# flexdrive_atlas_stack_draft_01.net
KiCad netlist of a schematic drawn in EAGLE
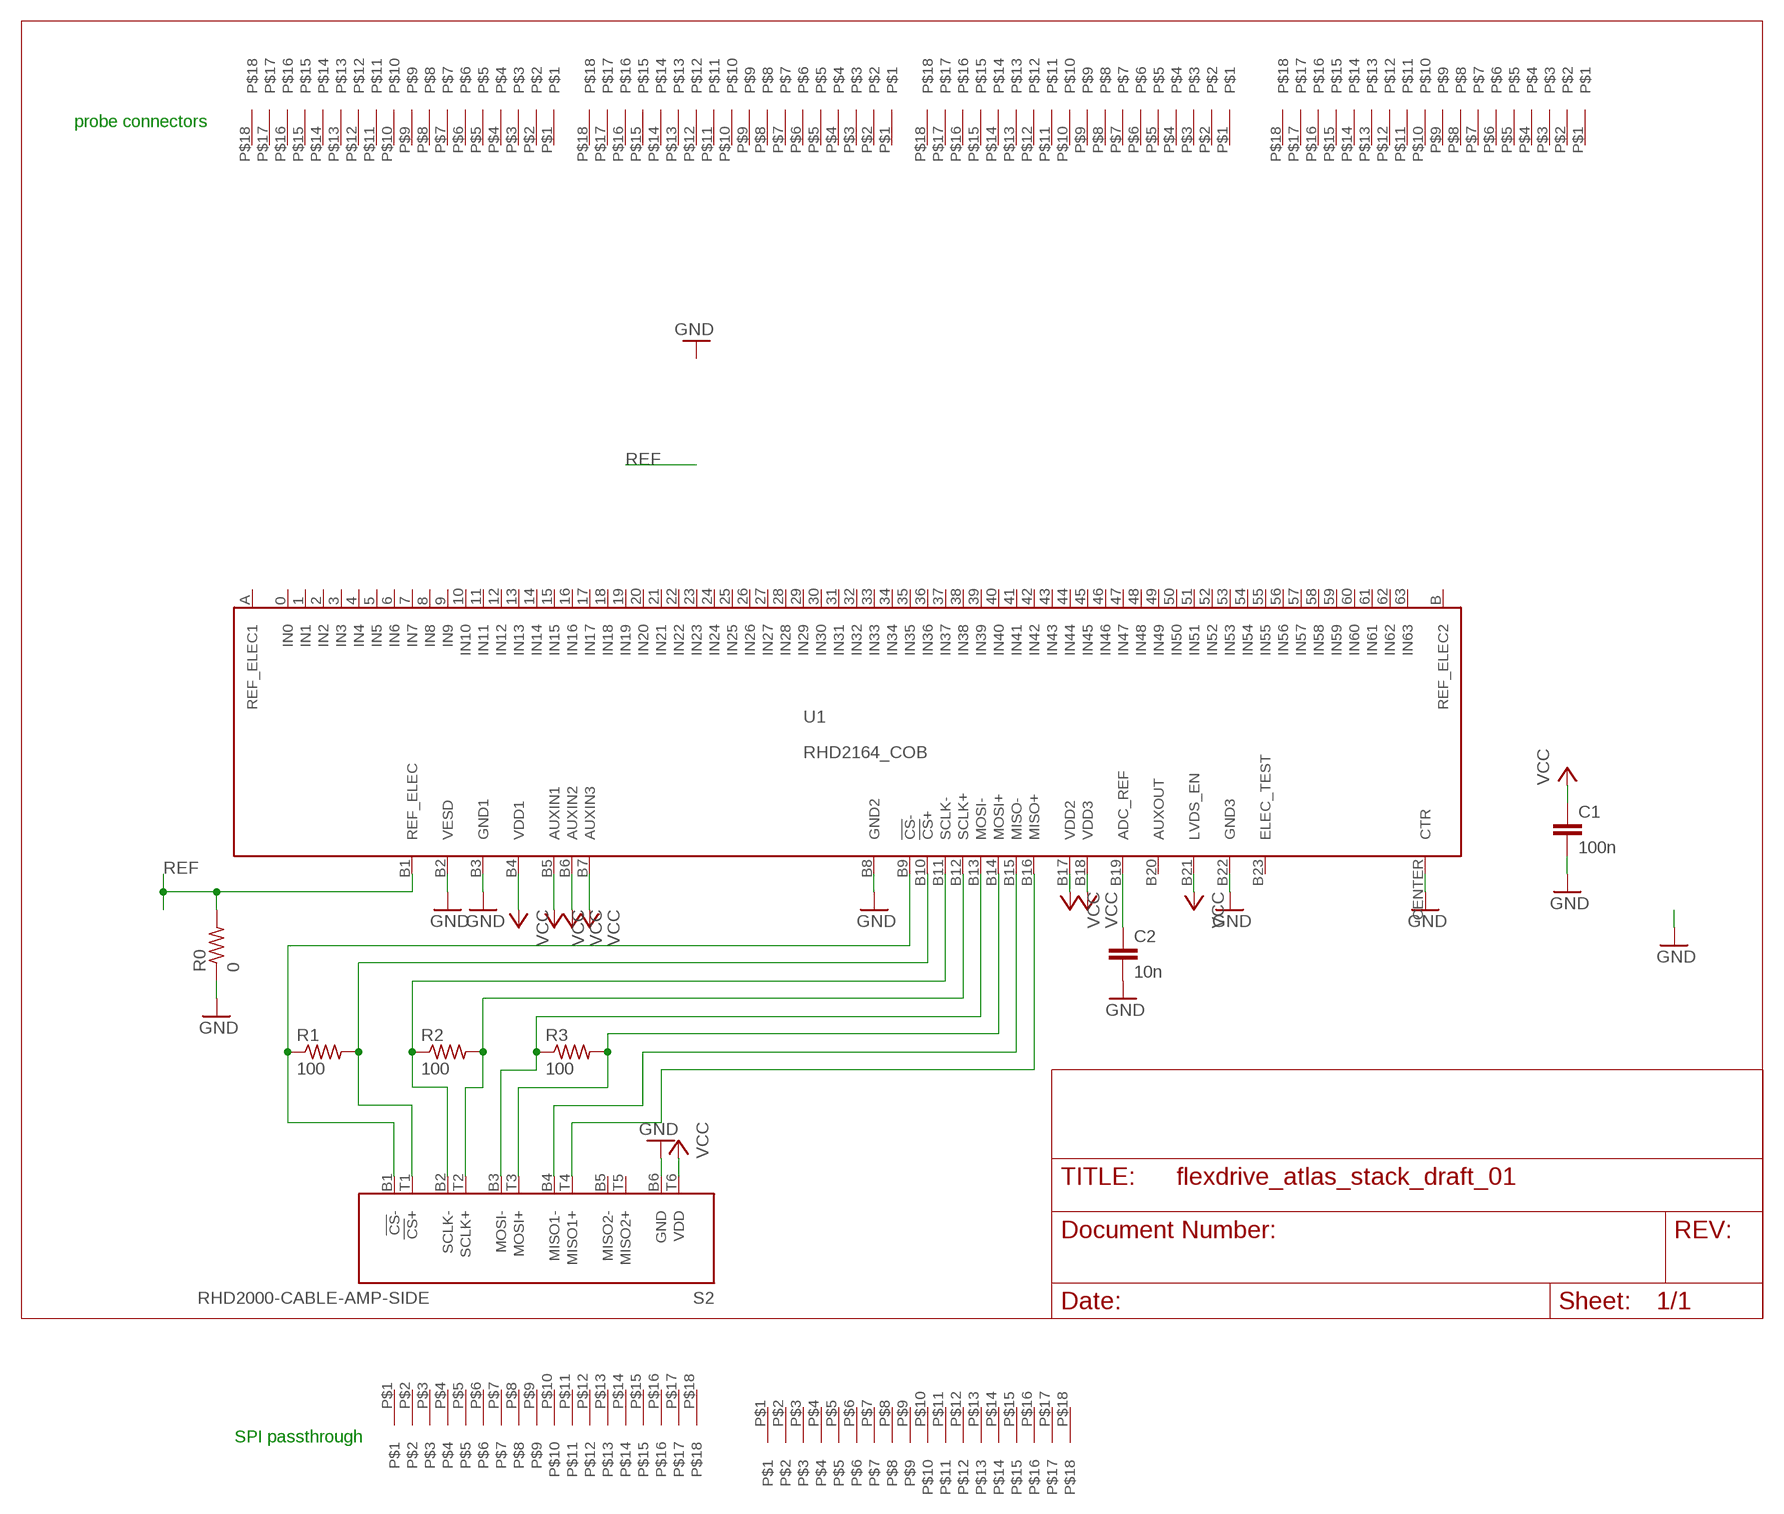
[diagram p0: schematic, sheet 1]

(export (version "E")
  (design (tool "Eeschema 10.0.6"))
  (components
    (comp (ref "C1")
      (value "100n")
      (footprint "eagle-import:0402")
      (libsource (lib "eagle-import") (part "C_0402"))
    )
    (comp (ref "C2")
      (value "10n")
      (footprint "eagle-import:0201")
      (libsource (lib "eagle-import") (part "C_0201"))
    )
    (comp (ref "R0")
      (value "0")
      (footprint "eagle-import:0402")
      (libsource (lib "eagle-import") (part "R_0402"))
    )
    (comp (ref "R1")
      (value "100")
      (footprint "eagle-import:0201")
      (libsource (lib "eagle-import") (part "R_0201"))
    )
    (comp (ref "R2")
      (value "100")
      (footprint "eagle-import:0201")
      (libsource (lib "eagle-import") (part "R_0201"))
    )
    (comp (ref "R3")
      (value "100")
      (footprint "eagle-import:0201")
      (libsource (lib "eagle-import") (part "R_0201"))
    )
    (comp (ref "S2")
      (value "RHD2000-CABLE-AMP-SIDE")
      (footprint "eagle-import:OMNETICS_PZN-12-AA")
      (libsource (lib "eagle-import") (part "RHD2000-CABLE-AMP-SIDE"))
    )
    (comp (ref "U$1")
      (value "18PIN_035MM_SLIMSTACK")
      (footprint "eagle-import:18PIN_025MM_SLIMSTACK")
      (libsource (lib "eagle-import") (part "18PIN_035MM_SLIMSTACK"))
    )
    (comp (ref "U$2")
      (value "18PIN_035MM_SLIMSTACK")
      (footprint "eagle-import:18PIN_025MM_SLIMSTACK")
      (libsource (lib "eagle-import") (part "18PIN_035MM_SLIMSTACK"))
    )
    (comp (ref "U$3")
      (value "18PIN_035MM_SLIMSTACK")
      (footprint "eagle-import:18PIN_025MM_SLIMSTACK")
      (libsource (lib "eagle-import") (part "18PIN_035MM_SLIMSTACK"))
    )
    (comp (ref "U$4")
      (value "18PIN_035MM_SLIMSTACK")
      (footprint "eagle-import:18PIN_025MM_SLIMSTACK")
      (libsource (lib "eagle-import") (part "18PIN_035MM_SLIMSTACK"))
    )
    (comp (ref "U$5")
      (value "18PIN_035MM_SLIMSTACK")
      (footprint "eagle-import:18PIN_025MM_SLIMSTACK")
      (libsource (lib "eagle-import") (part "18PIN_035MM_SLIMSTACK"))
    )
    (comp (ref "U$6")
      (value "18PIN_035MM_SLIMSTACK")
      (footprint "eagle-import:18PIN_025MM_SLIMSTACK")
      (libsource (lib "eagle-import") (part "18PIN_035MM_SLIMSTACK"))
    )
    (comp (ref "U1")
      (value "RHD2164_COB")
      (footprint "eagle-import:RHD2164_COB")
      (libsource (lib "eagle-import") (part "RHD2164_COB"))
    )
  )
  (nets
    (net (code "1") (name "/REF") (class "Default")
      (node (ref "R0") (pin "2") (pinfunction "2_2") (pintype "passive"))
      (node (ref "U1") (pin "B1") (pinfunction "REF_ELEC_B1") (pintype "input"))
    )
    (net (code "2") (name "GND") (class "Default")
      (node (ref "C1") (pin "2") (pinfunction "2_2") (pintype "passive"))
      (node (ref "C2") (pin "2") (pinfunction "2_2") (pintype "passive"))
      (node (ref "R0") (pin "1") (pinfunction "1_1") (pintype "passive"))
      (node (ref "S2") (pin "B6") (pinfunction "GND_B6") (pintype "power_in"))
      (node (ref "U1") (pin "B2") (pinfunction "VESD_B2") (pintype "power_in"))
      (node (ref "U1") (pin "B22") (pinfunction "GND3_B22") (pintype "power_in"))
      (node (ref "U1") (pin "B3") (pinfunction "GND1_B3") (pintype "power_in"))
      (node (ref "U1") (pin "B8") (pinfunction "GND2_B8") (pintype "power_in"))
      (node (ref "U1") (pin "CENTER") (pinfunction "CTR_CENTER") (pintype "power_in"))
    )
    (net (code "3") (name "Net-(S2-MISO1+)") (class "Default")
      (node (ref "S2") (pin "T4") (pinfunction "MISO1+_T4") (pintype "bidirectional"))
      (node (ref "U1") (pin "B16") (pinfunction "MISO+_B16") (pintype "output"))
    )
    (net (code "4") (name "Net-(S2-MISO1-)") (class "Default")
      (node (ref "S2") (pin "B4") (pinfunction "MISO1-_B4") (pintype "bidirectional"))
      (node (ref "U1") (pin "B15") (pinfunction "MISO-_B15") (pintype "output"))
    )
    (net (code "5") (name "Net-(S2-MOSI+)") (class "Default")
      (node (ref "R3") (pin "2") (pinfunction "2_2") (pintype "passive"))
      (node (ref "S2") (pin "T3") (pinfunction "MOSI+_T3") (pintype "bidirectional"))
      (node (ref "U1") (pin "B14") (pinfunction "MOSI+_B14") (pintype "input"))
    )
    (net (code "6") (name "Net-(S2-MOSI-)") (class "Default")
      (node (ref "R3") (pin "1") (pinfunction "1_1") (pintype "passive"))
      (node (ref "S2") (pin "B3") (pinfunction "MOSI-_B3") (pintype "bidirectional"))
      (node (ref "U1") (pin "B13") (pinfunction "MOSI-_B13") (pintype "input"))
    )
    (net (code "7") (name "Net-(S2-SCLK+)") (class "Default")
      (node (ref "R2") (pin "2") (pinfunction "2_2") (pintype "passive"))
      (node (ref "S2") (pin "T2") (pinfunction "SCLK+_T2") (pintype "bidirectional"))
      (node (ref "U1") (pin "B12") (pinfunction "SCLK+_B12") (pintype "input"))
    )
    (net (code "8") (name "Net-(S2-SCLK-)") (class "Default")
      (node (ref "R2") (pin "1") (pinfunction "1_1") (pintype "passive"))
      (node (ref "S2") (pin "B2") (pinfunction "SCLK-_B2") (pintype "bidirectional"))
      (node (ref "U1") (pin "B11") (pinfunction "SCLK-_B11") (pintype "input"))
    )
    (net (code "9") (name "Net-(S2-~{CS}+)") (class "Default")
      (node (ref "R1") (pin "2") (pinfunction "2_2") (pintype "passive"))
      (node (ref "S2") (pin "T1") (pinfunction "~{CS}+_T1") (pintype "bidirectional"))
      (node (ref "U1") (pin "B10") (pinfunction "~{CS}+_B10") (pintype "input"))
    )
    (net (code "10") (name "Net-(S2-~{CS}-)") (class "Default")
      (node (ref "R1") (pin "1") (pinfunction "1_1") (pintype "passive"))
      (node (ref "S2") (pin "B1") (pinfunction "~{CS}-_B1") (pintype "bidirectional"))
      (node (ref "U1") (pin "B9") (pinfunction "~{CS}-_B9") (pintype "input"))
    )
    (net (code "11") (name "Net-(U1-ADC_REF)") (class "Default")
      (node (ref "C2") (pin "1") (pinfunction "1_1") (pintype "passive"))
      (node (ref "U1") (pin "B19") (pinfunction "ADC_REF_B19") (pintype "passive"))
    )
    (net (code "12") (name "VCC") (class "Default")
      (node (ref "C1") (pin "1") (pinfunction "1_1") (pintype "passive"))
      (node (ref "S2") (pin "T6") (pinfunction "VDD_T6") (pintype "bidirectional"))
      (node (ref "U1") (pin "B17") (pinfunction "VDD2_B17") (pintype "power_in"))
      (node (ref "U1") (pin "B18") (pinfunction "VDD3_B18") (pintype "power_in"))
      (node (ref "U1") (pin "B21") (pinfunction "LVDS_EN_B21") (pintype "input"))
      (node (ref "U1") (pin "B4") (pinfunction "VDD1_B4") (pintype "power_in"))
      (node (ref "U1") (pin "B5") (pinfunction "AUXIN1_B5") (pintype "input"))
      (node (ref "U1") (pin "B6") (pinfunction "AUXIN2_B6") (pintype "input"))
      (node (ref "U1") (pin "B7") (pinfunction "AUXIN3_B7") (pintype "input"))
    )
    (net (code "13") (name "unconnected-(S2-MISO2+-PadT5)") (class "Default")
      (node (ref "S2") (pin "T5") (pinfunction "MISO2+_T5") (pintype "bidirectional"))
    )
    (net (code "14") (name "unconnected-(S2-MISO2--PadB5)") (class "Default")
      (node (ref "S2") (pin "B5") (pinfunction "MISO2-_B5") (pintype "bidirectional"))
    )
    (net (code "15") (name "unconnected-(U$1-PadP$1)") (class "Default")
      (node (ref "U$1") (pin "P$1") (pinfunction "P$1_P$1") (pintype "bidirectional"))
    )
    (net (code "16") (name "unconnected-(U$1-PadP$2)") (class "Default")
      (node (ref "U$1") (pin "P$2") (pinfunction "P$2_P$2") (pintype "bidirectional"))
    )
    (net (code "17") (name "unconnected-(U$1-PadP$3)") (class "Default")
      (node (ref "U$1") (pin "P$3") (pinfunction "P$3_P$3") (pintype "bidirectional"))
    )
    (net (code "18") (name "unconnected-(U$1-PadP$4)") (class "Default")
      (node (ref "U$1") (pin "P$4") (pinfunction "P$4_P$4") (pintype "bidirectional"))
    )
    (net (code "19") (name "unconnected-(U$1-PadP$5)") (class "Default")
      (node (ref "U$1") (pin "P$5") (pinfunction "P$5_P$5") (pintype "bidirectional"))
    )
    (net (code "20") (name "unconnected-(U$1-PadP$6)") (class "Default")
      (node (ref "U$1") (pin "P$6") (pinfunction "P$6_P$6") (pintype "bidirectional"))
    )
    (net (code "21") (name "unconnected-(U$1-PadP$7)") (class "Default")
      (node (ref "U$1") (pin "P$7") (pinfunction "P$7_P$7") (pintype "bidirectional"))
    )
    (net (code "22") (name "unconnected-(U$1-PadP$8)") (class "Default")
      (node (ref "U$1") (pin "P$8") (pinfunction "P$8_P$8") (pintype "bidirectional"))
    )
    (net (code "23") (name "unconnected-(U$1-PadP$9)") (class "Default")
      (node (ref "U$1") (pin "P$9") (pinfunction "P$9_P$9") (pintype "bidirectional"))
    )
    (net (code "24") (name "unconnected-(U$1-PadP$10)") (class "Default")
      (node (ref "U$1") (pin "P$10") (pinfunction "P$10_P$10") (pintype "bidirectional"))
    )
    (net (code "25") (name "unconnected-(U$1-PadP$11)") (class "Default")
      (node (ref "U$1") (pin "P$11") (pinfunction "P$11_P$11") (pintype "bidirectional"))
    )
    (net (code "26") (name "unconnected-(U$1-PadP$12)") (class "Default")
      (node (ref "U$1") (pin "P$12") (pinfunction "P$12_P$12") (pintype "bidirectional"))
    )
    (net (code "27") (name "unconnected-(U$1-PadP$13)") (class "Default")
      (node (ref "U$1") (pin "P$13") (pinfunction "P$13_P$13") (pintype "bidirectional"))
    )
    (net (code "28") (name "unconnected-(U$1-PadP$14)") (class "Default")
      (node (ref "U$1") (pin "P$14") (pinfunction "P$14_P$14") (pintype "bidirectional"))
    )
    (net (code "29") (name "unconnected-(U$1-PadP$15)") (class "Default")
      (node (ref "U$1") (pin "P$15") (pinfunction "P$15_P$15") (pintype "bidirectional"))
    )
    (net (code "30") (name "unconnected-(U$1-PadP$16)") (class "Default")
      (node (ref "U$1") (pin "P$16") (pinfunction "P$16_P$16") (pintype "bidirectional"))
    )
    (net (code "31") (name "unconnected-(U$1-PadP$17)") (class "Default")
      (node (ref "U$1") (pin "P$17") (pinfunction "P$17_P$17") (pintype "bidirectional"))
    )
    (net (code "32") (name "unconnected-(U$1-PadP$18)") (class "Default")
      (node (ref "U$1") (pin "P$18") (pinfunction "P$18_P$18") (pintype "bidirectional"))
    )
    (net (code "33") (name "unconnected-(U$2-PadP$1)") (class "Default")
      (node (ref "U$2") (pin "P$1") (pinfunction "P$1_P$1") (pintype "bidirectional"))
    )
    (net (code "34") (name "unconnected-(U$2-PadP$2)") (class "Default")
      (node (ref "U$2") (pin "P$2") (pinfunction "P$2_P$2") (pintype "bidirectional"))
    )
    (net (code "35") (name "unconnected-(U$2-PadP$3)") (class "Default")
      (node (ref "U$2") (pin "P$3") (pinfunction "P$3_P$3") (pintype "bidirectional"))
    )
    (net (code "36") (name "unconnected-(U$2-PadP$4)") (class "Default")
      (node (ref "U$2") (pin "P$4") (pinfunction "P$4_P$4") (pintype "bidirectional"))
    )
    (net (code "37") (name "unconnected-(U$2-PadP$5)") (class "Default")
      (node (ref "U$2") (pin "P$5") (pinfunction "P$5_P$5") (pintype "bidirectional"))
    )
    (net (code "38") (name "unconnected-(U$2-PadP$6)") (class "Default")
      (node (ref "U$2") (pin "P$6") (pinfunction "P$6_P$6") (pintype "bidirectional"))
    )
    (net (code "39") (name "unconnected-(U$2-PadP$7)") (class "Default")
      (node (ref "U$2") (pin "P$7") (pinfunction "P$7_P$7") (pintype "bidirectional"))
    )
    (net (code "40") (name "unconnected-(U$2-PadP$8)") (class "Default")
      (node (ref "U$2") (pin "P$8") (pinfunction "P$8_P$8") (pintype "bidirectional"))
    )
    (net (code "41") (name "unconnected-(U$2-PadP$9)") (class "Default")
      (node (ref "U$2") (pin "P$9") (pinfunction "P$9_P$9") (pintype "bidirectional"))
    )
    (net (code "42") (name "unconnected-(U$2-PadP$10)") (class "Default")
      (node (ref "U$2") (pin "P$10") (pinfunction "P$10_P$10") (pintype "bidirectional"))
    )
    (net (code "43") (name "unconnected-(U$2-PadP$11)") (class "Default")
      (node (ref "U$2") (pin "P$11") (pinfunction "P$11_P$11") (pintype "bidirectional"))
    )
    (net (code "44") (name "unconnected-(U$2-PadP$12)") (class "Default")
      (node (ref "U$2") (pin "P$12") (pinfunction "P$12_P$12") (pintype "bidirectional"))
    )
    (net (code "45") (name "unconnected-(U$2-PadP$13)") (class "Default")
      (node (ref "U$2") (pin "P$13") (pinfunction "P$13_P$13") (pintype "bidirectional"))
    )
    (net (code "46") (name "unconnected-(U$2-PadP$14)") (class "Default")
      (node (ref "U$2") (pin "P$14") (pinfunction "P$14_P$14") (pintype "bidirectional"))
    )
    (net (code "47") (name "unconnected-(U$2-PadP$15)") (class "Default")
      (node (ref "U$2") (pin "P$15") (pinfunction "P$15_P$15") (pintype "bidirectional"))
    )
    (net (code "48") (name "unconnected-(U$2-PadP$16)") (class "Default")
      (node (ref "U$2") (pin "P$16") (pinfunction "P$16_P$16") (pintype "bidirectional"))
    )
    (net (code "49") (name "unconnected-(U$2-PadP$17)") (class "Default")
      (node (ref "U$2") (pin "P$17") (pinfunction "P$17_P$17") (pintype "bidirectional"))
    )
    (net (code "50") (name "unconnected-(U$2-PadP$18)") (class "Default")
      (node (ref "U$2") (pin "P$18") (pinfunction "P$18_P$18") (pintype "bidirectional"))
    )
    (net (code "51") (name "unconnected-(U$3-PadP$1)") (class "Default")
      (node (ref "U$3") (pin "P$1") (pinfunction "P$1_P$1") (pintype "bidirectional"))
    )
    (net (code "52") (name "unconnected-(U$3-PadP$2)") (class "Default")
      (node (ref "U$3") (pin "P$2") (pinfunction "P$2_P$2") (pintype "bidirectional"))
    )
    (net (code "53") (name "unconnected-(U$3-PadP$3)") (class "Default")
      (node (ref "U$3") (pin "P$3") (pinfunction "P$3_P$3") (pintype "bidirectional"))
    )
    (net (code "54") (name "unconnected-(U$3-PadP$4)") (class "Default")
      (node (ref "U$3") (pin "P$4") (pinfunction "P$4_P$4") (pintype "bidirectional"))
    )
    (net (code "55") (name "unconnected-(U$3-PadP$5)") (class "Default")
      (node (ref "U$3") (pin "P$5") (pinfunction "P$5_P$5") (pintype "bidirectional"))
    )
    (net (code "56") (name "unconnected-(U$3-PadP$6)") (class "Default")
      (node (ref "U$3") (pin "P$6") (pinfunction "P$6_P$6") (pintype "bidirectional"))
    )
    (net (code "57") (name "unconnected-(U$3-PadP$7)") (class "Default")
      (node (ref "U$3") (pin "P$7") (pinfunction "P$7_P$7") (pintype "bidirectional"))
    )
    (net (code "58") (name "unconnected-(U$3-PadP$8)") (class "Default")
      (node (ref "U$3") (pin "P$8") (pinfunction "P$8_P$8") (pintype "bidirectional"))
    )
    (net (code "59") (name "unconnected-(U$3-PadP$9)") (class "Default")
      (node (ref "U$3") (pin "P$9") (pinfunction "P$9_P$9") (pintype "bidirectional"))
    )
    (net (code "60") (name "unconnected-(U$3-PadP$10)") (class "Default")
      (node (ref "U$3") (pin "P$10") (pinfunction "P$10_P$10") (pintype "bidirectional"))
    )
    (net (code "61") (name "unconnected-(U$3-PadP$11)") (class "Default")
      (node (ref "U$3") (pin "P$11") (pinfunction "P$11_P$11") (pintype "bidirectional"))
    )
    (net (code "62") (name "unconnected-(U$3-PadP$12)") (class "Default")
      (node (ref "U$3") (pin "P$12") (pinfunction "P$12_P$12") (pintype "bidirectional"))
    )
    (net (code "63") (name "unconnected-(U$3-PadP$13)") (class "Default")
      (node (ref "U$3") (pin "P$13") (pinfunction "P$13_P$13") (pintype "bidirectional"))
    )
    (net (code "64") (name "unconnected-(U$3-PadP$14)") (class "Default")
      (node (ref "U$3") (pin "P$14") (pinfunction "P$14_P$14") (pintype "bidirectional"))
    )
    (net (code "65") (name "unconnected-(U$3-PadP$15)") (class "Default")
      (node (ref "U$3") (pin "P$15") (pinfunction "P$15_P$15") (pintype "bidirectional"))
    )
    (net (code "66") (name "unconnected-(U$3-PadP$16)") (class "Default")
      (node (ref "U$3") (pin "P$16") (pinfunction "P$16_P$16") (pintype "bidirectional"))
    )
    (net (code "67") (name "unconnected-(U$3-PadP$17)") (class "Default")
      (node (ref "U$3") (pin "P$17") (pinfunction "P$17_P$17") (pintype "bidirectional"))
    )
    (net (code "68") (name "unconnected-(U$3-PadP$18)") (class "Default")
      (node (ref "U$3") (pin "P$18") (pinfunction "P$18_P$18") (pintype "bidirectional"))
    )
    (net (code "69") (name "unconnected-(U$4-PadP$1)") (class "Default")
      (node (ref "U$4") (pin "P$1") (pinfunction "P$1_P$1") (pintype "bidirectional"))
    )
    (net (code "70") (name "unconnected-(U$4-PadP$2)") (class "Default")
      (node (ref "U$4") (pin "P$2") (pinfunction "P$2_P$2") (pintype "bidirectional"))
    )
    (net (code "71") (name "unconnected-(U$4-PadP$3)") (class "Default")
      (node (ref "U$4") (pin "P$3") (pinfunction "P$3_P$3") (pintype "bidirectional"))
    )
    (net (code "72") (name "unconnected-(U$4-PadP$4)") (class "Default")
      (node (ref "U$4") (pin "P$4") (pinfunction "P$4_P$4") (pintype "bidirectional"))
    )
    (net (code "73") (name "unconnected-(U$4-PadP$5)") (class "Default")
      (node (ref "U$4") (pin "P$5") (pinfunction "P$5_P$5") (pintype "bidirectional"))
    )
    (net (code "74") (name "unconnected-(U$4-PadP$6)") (class "Default")
      (node (ref "U$4") (pin "P$6") (pinfunction "P$6_P$6") (pintype "bidirectional"))
    )
    (net (code "75") (name "unconnected-(U$4-PadP$7)") (class "Default")
      (node (ref "U$4") (pin "P$7") (pinfunction "P$7_P$7") (pintype "bidirectional"))
    )
    (net (code "76") (name "unconnected-(U$4-PadP$8)") (class "Default")
      (node (ref "U$4") (pin "P$8") (pinfunction "P$8_P$8") (pintype "bidirectional"))
    )
    (net (code "77") (name "unconnected-(U$4-PadP$9)") (class "Default")
      (node (ref "U$4") (pin "P$9") (pinfunction "P$9_P$9") (pintype "bidirectional"))
    )
    (net (code "78") (name "unconnected-(U$4-PadP$10)") (class "Default")
      (node (ref "U$4") (pin "P$10") (pinfunction "P$10_P$10") (pintype "bidirectional"))
    )
    (net (code "79") (name "unconnected-(U$4-PadP$11)") (class "Default")
      (node (ref "U$4") (pin "P$11") (pinfunction "P$11_P$11") (pintype "bidirectional"))
    )
    (net (code "80") (name "unconnected-(U$4-PadP$12)") (class "Default")
      (node (ref "U$4") (pin "P$12") (pinfunction "P$12_P$12") (pintype "bidirectional"))
    )
    (net (code "81") (name "unconnected-(U$4-PadP$13)") (class "Default")
      (node (ref "U$4") (pin "P$13") (pinfunction "P$13_P$13") (pintype "bidirectional"))
    )
    (net (code "82") (name "unconnected-(U$4-PadP$14)") (class "Default")
      (node (ref "U$4") (pin "P$14") (pinfunction "P$14_P$14") (pintype "bidirectional"))
    )
    (net (code "83") (name "unconnected-(U$4-PadP$15)") (class "Default")
      (node (ref "U$4") (pin "P$15") (pinfunction "P$15_P$15") (pintype "bidirectional"))
    )
    (net (code "84") (name "unconnected-(U$4-PadP$16)") (class "Default")
      (node (ref "U$4") (pin "P$16") (pinfunction "P$16_P$16") (pintype "bidirectional"))
    )
    (net (code "85") (name "unconnected-(U$4-PadP$17)") (class "Default")
      (node (ref "U$4") (pin "P$17") (pinfunction "P$17_P$17") (pintype "bidirectional"))
    )
    (net (code "86") (name "unconnected-(U$4-PadP$18)") (class "Default")
      (node (ref "U$4") (pin "P$18") (pinfunction "P$18_P$18") (pintype "bidirectional"))
    )
    (net (code "87") (name "unconnected-(U$5-PadP$1)") (class "Default")
      (node (ref "U$5") (pin "P$1") (pinfunction "P$1_P$1") (pintype "bidirectional"))
    )
    (net (code "88") (name "unconnected-(U$5-PadP$2)") (class "Default")
      (node (ref "U$5") (pin "P$2") (pinfunction "P$2_P$2") (pintype "bidirectional"))
    )
    (net (code "89") (name "unconnected-(U$5-PadP$3)") (class "Default")
      (node (ref "U$5") (pin "P$3") (pinfunction "P$3_P$3") (pintype "bidirectional"))
    )
    (net (code "90") (name "unconnected-(U$5-PadP$4)") (class "Default")
      (node (ref "U$5") (pin "P$4") (pinfunction "P$4_P$4") (pintype "bidirectional"))
    )
    (net (code "91") (name "unconnected-(U$5-PadP$5)") (class "Default")
      (node (ref "U$5") (pin "P$5") (pinfunction "P$5_P$5") (pintype "bidirectional"))
    )
    (net (code "92") (name "unconnected-(U$5-PadP$6)") (class "Default")
      (node (ref "U$5") (pin "P$6") (pinfunction "P$6_P$6") (pintype "bidirectional"))
    )
    (net (code "93") (name "unconnected-(U$5-PadP$7)") (class "Default")
      (node (ref "U$5") (pin "P$7") (pinfunction "P$7_P$7") (pintype "bidirectional"))
    )
    (net (code "94") (name "unconnected-(U$5-PadP$8)") (class "Default")
      (node (ref "U$5") (pin "P$8") (pinfunction "P$8_P$8") (pintype "bidirectional"))
    )
    (net (code "95") (name "unconnected-(U$5-PadP$9)") (class "Default")
      (node (ref "U$5") (pin "P$9") (pinfunction "P$9_P$9") (pintype "bidirectional"))
    )
    (net (code "96") (name "unconnected-(U$5-PadP$10)") (class "Default")
      (node (ref "U$5") (pin "P$10") (pinfunction "P$10_P$10") (pintype "bidirectional"))
    )
    (net (code "97") (name "unconnected-(U$5-PadP$11)") (class "Default")
      (node (ref "U$5") (pin "P$11") (pinfunction "P$11_P$11") (pintype "bidirectional"))
    )
    (net (code "98") (name "unconnected-(U$5-PadP$12)") (class "Default")
      (node (ref "U$5") (pin "P$12") (pinfunction "P$12_P$12") (pintype "bidirectional"))
    )
    (net (code "99") (name "unconnected-(U$5-PadP$13)") (class "Default")
      (node (ref "U$5") (pin "P$13") (pinfunction "P$13_P$13") (pintype "bidirectional"))
    )
    (net (code "100") (name "unconnected-(U$5-PadP$14)") (class "Default")
      (node (ref "U$5") (pin "P$14") (pinfunction "P$14_P$14") (pintype "bidirectional"))
    )
    (net (code "101") (name "unconnected-(U$5-PadP$15)") (class "Default")
      (node (ref "U$5") (pin "P$15") (pinfunction "P$15_P$15") (pintype "bidirectional"))
    )
    (net (code "102") (name "unconnected-(U$5-PadP$16)") (class "Default")
      (node (ref "U$5") (pin "P$16") (pinfunction "P$16_P$16") (pintype "bidirectional"))
    )
    (net (code "103") (name "unconnected-(U$5-PadP$17)") (class "Default")
      (node (ref "U$5") (pin "P$17") (pinfunction "P$17_P$17") (pintype "bidirectional"))
    )
    (net (code "104") (name "unconnected-(U$5-PadP$18)") (class "Default")
      (node (ref "U$5") (pin "P$18") (pinfunction "P$18_P$18") (pintype "bidirectional"))
    )
    (net (code "105") (name "unconnected-(U$6-PadP$1)") (class "Default")
      (node (ref "U$6") (pin "P$1") (pinfunction "P$1_P$1") (pintype "bidirectional"))
    )
    (net (code "106") (name "unconnected-(U$6-PadP$2)") (class "Default")
      (node (ref "U$6") (pin "P$2") (pinfunction "P$2_P$2") (pintype "bidirectional"))
    )
    (net (code "107") (name "unconnected-(U$6-PadP$3)") (class "Default")
      (node (ref "U$6") (pin "P$3") (pinfunction "P$3_P$3") (pintype "bidirectional"))
    )
    (net (code "108") (name "unconnected-(U$6-PadP$4)") (class "Default")
      (node (ref "U$6") (pin "P$4") (pinfunction "P$4_P$4") (pintype "bidirectional"))
    )
    (net (code "109") (name "unconnected-(U$6-PadP$5)") (class "Default")
      (node (ref "U$6") (pin "P$5") (pinfunction "P$5_P$5") (pintype "bidirectional"))
    )
    (net (code "110") (name "unconnected-(U$6-PadP$6)") (class "Default")
      (node (ref "U$6") (pin "P$6") (pinfunction "P$6_P$6") (pintype "bidirectional"))
    )
    (net (code "111") (name "unconnected-(U$6-PadP$7)") (class "Default")
      (node (ref "U$6") (pin "P$7") (pinfunction "P$7_P$7") (pintype "bidirectional"))
    )
    (net (code "112") (name "unconnected-(U$6-PadP$8)") (class "Default")
      (node (ref "U$6") (pin "P$8") (pinfunction "P$8_P$8") (pintype "bidirectional"))
    )
    (net (code "113") (name "unconnected-(U$6-PadP$9)") (class "Default")
      (node (ref "U$6") (pin "P$9") (pinfunction "P$9_P$9") (pintype "bidirectional"))
    )
    (net (code "114") (name "unconnected-(U$6-PadP$10)") (class "Default")
      (node (ref "U$6") (pin "P$10") (pinfunction "P$10_P$10") (pintype "bidirectional"))
    )
    (net (code "115") (name "unconnected-(U$6-PadP$11)") (class "Default")
      (node (ref "U$6") (pin "P$11") (pinfunction "P$11_P$11") (pintype "bidirectional"))
    )
    (net (code "116") (name "unconnected-(U$6-PadP$12)") (class "Default")
      (node (ref "U$6") (pin "P$12") (pinfunction "P$12_P$12") (pintype "bidirectional"))
    )
    (net (code "117") (name "unconnected-(U$6-PadP$13)") (class "Default")
      (node (ref "U$6") (pin "P$13") (pinfunction "P$13_P$13") (pintype "bidirectional"))
    )
    (net (code "118") (name "unconnected-(U$6-PadP$14)") (class "Default")
      (node (ref "U$6") (pin "P$14") (pinfunction "P$14_P$14") (pintype "bidirectional"))
    )
    (net (code "119") (name "unconnected-(U$6-PadP$15)") (class "Default")
      (node (ref "U$6") (pin "P$15") (pinfunction "P$15_P$15") (pintype "bidirectional"))
    )
    (net (code "120") (name "unconnected-(U$6-PadP$16)") (class "Default")
      (node (ref "U$6") (pin "P$16") (pinfunction "P$16_P$16") (pintype "bidirectional"))
    )
    (net (code "121") (name "unconnected-(U$6-PadP$17)") (class "Default")
      (node (ref "U$6") (pin "P$17") (pinfunction "P$17_P$17") (pintype "bidirectional"))
    )
    (net (code "122") (name "unconnected-(U$6-PadP$18)") (class "Default")
      (node (ref "U$6") (pin "P$18") (pinfunction "P$18_P$18") (pintype "bidirectional"))
    )
    (net (code "123") (name "unconnected-(U1-AUXOUT-PadB20)") (class "Default")
      (node (ref "U1") (pin "B20") (pinfunction "AUXOUT_B20") (pintype "tri_state"))
    )
    (net (code "124") (name "unconnected-(U1-ELEC_TEST-PadB23)") (class "Default")
      (node (ref "U1") (pin "B23") (pinfunction "ELEC_TEST_B23") (pintype "input"))
    )
    (net (code "125") (name "unconnected-(U1-IN0-Pad0)") (class "Default")
      (node (ref "U1") (pin "0") (pinfunction "IN0_0") (pintype "input"))
    )
    (net (code "126") (name "unconnected-(U1-IN1-Pad1)") (class "Default")
      (node (ref "U1") (pin "1") (pinfunction "IN1_1") (pintype "input"))
    )
    (net (code "127") (name "unconnected-(U1-IN2-Pad2)") (class "Default")
      (node (ref "U1") (pin "2") (pinfunction "IN2_2") (pintype "input"))
    )
    (net (code "128") (name "unconnected-(U1-IN3-Pad3)") (class "Default")
      (node (ref "U1") (pin "3") (pinfunction "IN3_3") (pintype "input"))
    )
    (net (code "129") (name "unconnected-(U1-IN4-Pad4)") (class "Default")
      (node (ref "U1") (pin "4") (pinfunction "IN4_4") (pintype "input"))
    )
    (net (code "130") (name "unconnected-(U1-IN5-Pad5)") (class "Default")
      (node (ref "U1") (pin "5") (pinfunction "IN5_5") (pintype "input"))
    )
    (net (code "131") (name "unconnected-(U1-IN6-Pad6)") (class "Default")
      (node (ref "U1") (pin "6") (pinfunction "IN6_6") (pintype "input"))
    )
    (net (code "132") (name "unconnected-(U1-IN7-Pad7)") (class "Default")
      (node (ref "U1") (pin "7") (pinfunction "IN7_7") (pintype "input"))
    )
    (net (code "133") (name "unconnected-(U1-IN8-Pad8)") (class "Default")
      (node (ref "U1") (pin "8") (pinfunction "IN8_8") (pintype "input"))
    )
    (net (code "134") (name "unconnected-(U1-IN9-Pad9)") (class "Default")
      (node (ref "U1") (pin "9") (pinfunction "IN9_9") (pintype "input"))
    )
    (net (code "135") (name "unconnected-(U1-IN10-Pad10)") (class "Default")
      (node (ref "U1") (pin "10") (pinfunction "IN10_10") (pintype "input"))
    )
    (net (code "136") (name "unconnected-(U1-IN11-Pad11)") (class "Default")
      (node (ref "U1") (pin "11") (pinfunction "IN11_11") (pintype "input"))
    )
    (net (code "137") (name "unconnected-(U1-IN12-Pad12)") (class "Default")
      (node (ref "U1") (pin "12") (pinfunction "IN12_12") (pintype "input"))
    )
    (net (code "138") (name "unconnected-(U1-IN13-Pad13)") (class "Default")
      (node (ref "U1") (pin "13") (pinfunction "IN13_13") (pintype "input"))
    )
    (net (code "139") (name "unconnected-(U1-IN14-Pad14)") (class "Default")
      (node (ref "U1") (pin "14") (pinfunction "IN14_14") (pintype "input"))
    )
    (net (code "140") (name "unconnected-(U1-IN15-Pad15)") (class "Default")
      (node (ref "U1") (pin "15") (pinfunction "IN15_15") (pintype "input"))
    )
    (net (code "141") (name "unconnected-(U1-IN16-Pad16)") (class "Default")
      (node (ref "U1") (pin "16") (pinfunction "IN16_16") (pintype "input"))
    )
    (net (code "142") (name "unconnected-(U1-IN17-Pad17)") (class "Default")
      (node (ref "U1") (pin "17") (pinfunction "IN17_17") (pintype "input"))
    )
    (net (code "143") (name "unconnected-(U1-IN18-Pad18)") (class "Default")
      (node (ref "U1") (pin "18") (pinfunction "IN18_18") (pintype "input"))
    )
    (net (code "144") (name "unconnected-(U1-IN19-Pad19)") (class "Default")
      (node (ref "U1") (pin "19") (pinfunction "IN19_19") (pintype "input"))
    )
    (net (code "145") (name "unconnected-(U1-IN20-Pad20)") (class "Default")
      (node (ref "U1") (pin "20") (pinfunction "IN20_20") (pintype "input"))
    )
    (net (code "146") (name "unconnected-(U1-IN21-Pad21)") (class "Default")
      (node (ref "U1") (pin "21") (pinfunction "IN21_21") (pintype "input"))
    )
    (net (code "147") (name "unconnected-(U1-IN22-Pad22)") (class "Default")
      (node (ref "U1") (pin "22") (pinfunction "IN22_22") (pintype "input"))
    )
    (net (code "148") (name "unconnected-(U1-IN23-Pad23)") (class "Default")
      (node (ref "U1") (pin "23") (pinfunction "IN23_23") (pintype "input"))
    )
    (net (code "149") (name "unconnected-(U1-IN24-Pad24)") (class "Default")
      (node (ref "U1") (pin "24") (pinfunction "IN24_24") (pintype "input"))
    )
    (net (code "150") (name "unconnected-(U1-IN25-Pad25)") (class "Default")
      (node (ref "U1") (pin "25") (pinfunction "IN25_25") (pintype "input"))
    )
    (net (code "151") (name "unconnected-(U1-IN26-Pad26)") (class "Default")
      (node (ref "U1") (pin "26") (pinfunction "IN26_26") (pintype "input"))
    )
    (net (code "152") (name "unconnected-(U1-IN27-Pad27)") (class "Default")
      (node (ref "U1") (pin "27") (pinfunction "IN27_27") (pintype "input"))
    )
    (net (code "153") (name "unconnected-(U1-IN28-Pad28)") (class "Default")
      (node (ref "U1") (pin "28") (pinfunction "IN28_28") (pintype "input"))
    )
    (net (code "154") (name "unconnected-(U1-IN29-Pad29)") (class "Default")
      (node (ref "U1") (pin "29") (pinfunction "IN29_29") (pintype "input"))
    )
    (net (code "155") (name "unconnected-(U1-IN30-Pad30)") (class "Default")
      (node (ref "U1") (pin "30") (pinfunction "IN30_30") (pintype "input"))
    )
    (net (code "156") (name "unconnected-(U1-IN31-Pad31)") (class "Default")
      (node (ref "U1") (pin "31") (pinfunction "IN31_31") (pintype "input"))
    )
    (net (code "157") (name "unconnected-(U1-IN32-Pad32)") (class "Default")
      (node (ref "U1") (pin "32") (pinfunction "IN32_32") (pintype "input"))
    )
    (net (code "158") (name "unconnected-(U1-IN33-Pad33)") (class "Default")
      (node (ref "U1") (pin "33") (pinfunction "IN33_33") (pintype "input"))
    )
    (net (code "159") (name "unconnected-(U1-IN34-Pad34)") (class "Default")
      (node (ref "U1") (pin "34") (pinfunction "IN34_34") (pintype "input"))
    )
    (net (code "160") (name "unconnected-(U1-IN35-Pad35)") (class "Default")
      (node (ref "U1") (pin "35") (pinfunction "IN35_35") (pintype "input"))
    )
    (net (code "161") (name "unconnected-(U1-IN36-Pad36)") (class "Default")
      (node (ref "U1") (pin "36") (pinfunction "IN36_36") (pintype "input"))
    )
    (net (code "162") (name "unconnected-(U1-IN37-Pad37)") (class "Default")
      (node (ref "U1") (pin "37") (pinfunction "IN37_37") (pintype "input"))
    )
    (net (code "163") (name "unconnected-(U1-IN38-Pad38)") (class "Default")
      (node (ref "U1") (pin "38") (pinfunction "IN38_38") (pintype "input"))
    )
    (net (code "164") (name "unconnected-(U1-IN39-Pad39)") (class "Default")
      (node (ref "U1") (pin "39") (pinfunction "IN39_39") (pintype "input"))
    )
    (net (code "165") (name "unconnected-(U1-IN40-Pad40)") (class "Default")
      (node (ref "U1") (pin "40") (pinfunction "IN40_40") (pintype "input"))
    )
    (net (code "166") (name "unconnected-(U1-IN41-Pad41)") (class "Default")
      (node (ref "U1") (pin "41") (pinfunction "IN41_41") (pintype "input"))
    )
    (net (code "167") (name "unconnected-(U1-IN42-Pad42)") (class "Default")
      (node (ref "U1") (pin "42") (pinfunction "IN42_42") (pintype "input"))
    )
    (net (code "168") (name "unconnected-(U1-IN43-Pad43)") (class "Default")
      (node (ref "U1") (pin "43") (pinfunction "IN43_43") (pintype "input"))
    )
    (net (code "169") (name "unconnected-(U1-IN44-Pad44)") (class "Default")
      (node (ref "U1") (pin "44") (pinfunction "IN44_44") (pintype "input"))
    )
    (net (code "170") (name "unconnected-(U1-IN45-Pad45)") (class "Default")
      (node (ref "U1") (pin "45") (pinfunction "IN45_45") (pintype "input"))
    )
    (net (code "171") (name "unconnected-(U1-IN46-Pad46)") (class "Default")
      (node (ref "U1") (pin "46") (pinfunction "IN46_46") (pintype "input"))
    )
    (net (code "172") (name "unconnected-(U1-IN47-Pad47)") (class "Default")
      (node (ref "U1") (pin "47") (pinfunction "IN47_47") (pintype "input"))
    )
    (net (code "173") (name "unconnected-(U1-IN48-Pad48)") (class "Default")
      (node (ref "U1") (pin "48") (pinfunction "IN48_48") (pintype "input"))
    )
    (net (code "174") (name "unconnected-(U1-IN49-Pad49)") (class "Default")
      (node (ref "U1") (pin "49") (pinfunction "IN49_49") (pintype "input"))
    )
    (net (code "175") (name "unconnected-(U1-IN50-Pad50)") (class "Default")
      (node (ref "U1") (pin "50") (pinfunction "IN50_50") (pintype "input"))
    )
    (net (code "176") (name "unconnected-(U1-IN51-Pad51)") (class "Default")
      (node (ref "U1") (pin "51") (pinfunction "IN51_51") (pintype "input"))
    )
    (net (code "177") (name "unconnected-(U1-IN52-Pad52)") (class "Default")
      (node (ref "U1") (pin "52") (pinfunction "IN52_52") (pintype "input"))
    )
    (net (code "178") (name "unconnected-(U1-IN53-Pad53)") (class "Default")
      (node (ref "U1") (pin "53") (pinfunction "IN53_53") (pintype "input"))
    )
    (net (code "179") (name "unconnected-(U1-IN54-Pad54)") (class "Default")
      (node (ref "U1") (pin "54") (pinfunction "IN54_54") (pintype "input"))
    )
    (net (code "180") (name "unconnected-(U1-IN55-Pad55)") (class "Default")
      (node (ref "U1") (pin "55") (pinfunction "IN55_55") (pintype "input"))
    )
    (net (code "181") (name "unconnected-(U1-IN56-Pad56)") (class "Default")
      (node (ref "U1") (pin "56") (pinfunction "IN56_56") (pintype "input"))
    )
    (net (code "182") (name "unconnected-(U1-IN57-Pad57)") (class "Default")
      (node (ref "U1") (pin "57") (pinfunction "IN57_57") (pintype "input"))
    )
    (net (code "183") (name "unconnected-(U1-IN58-Pad58)") (class "Default")
      (node (ref "U1") (pin "58") (pinfunction "IN58_58") (pintype "input"))
    )
    (net (code "184") (name "unconnected-(U1-IN59-Pad59)") (class "Default")
      (node (ref "U1") (pin "59") (pinfunction "IN59_59") (pintype "input"))
    )
    (net (code "185") (name "unconnected-(U1-IN60-Pad60)") (class "Default")
      (node (ref "U1") (pin "60") (pinfunction "IN60_60") (pintype "input"))
    )
    (net (code "186") (name "unconnected-(U1-IN61-Pad61)") (class "Default")
      (node (ref "U1") (pin "61") (pinfunction "IN61_61") (pintype "input"))
    )
    (net (code "187") (name "unconnected-(U1-IN62-Pad62)") (class "Default")
      (node (ref "U1") (pin "62") (pinfunction "IN62_62") (pintype "input"))
    )
    (net (code "188") (name "unconnected-(U1-IN63-Pad63)") (class "Default")
      (node (ref "U1") (pin "63") (pinfunction "IN63_63") (pintype "input"))
    )
    (net (code "189") (name "unconnected-(U1-REF_ELEC1-PadA)") (class "Default")
      (node (ref "U1") (pin "A") (pinfunction "REF_ELEC1_A") (pintype "input"))
    )
    (net (code "190") (name "unconnected-(U1-REF_ELEC2-PadB)") (class "Default")
      (node (ref "U1") (pin "B") (pinfunction "REF_ELEC2_B") (pintype "input"))
    )
  )
)
